# HS-IO-Top.net
KiCad netlist of a schematic drawn in Altium Designer
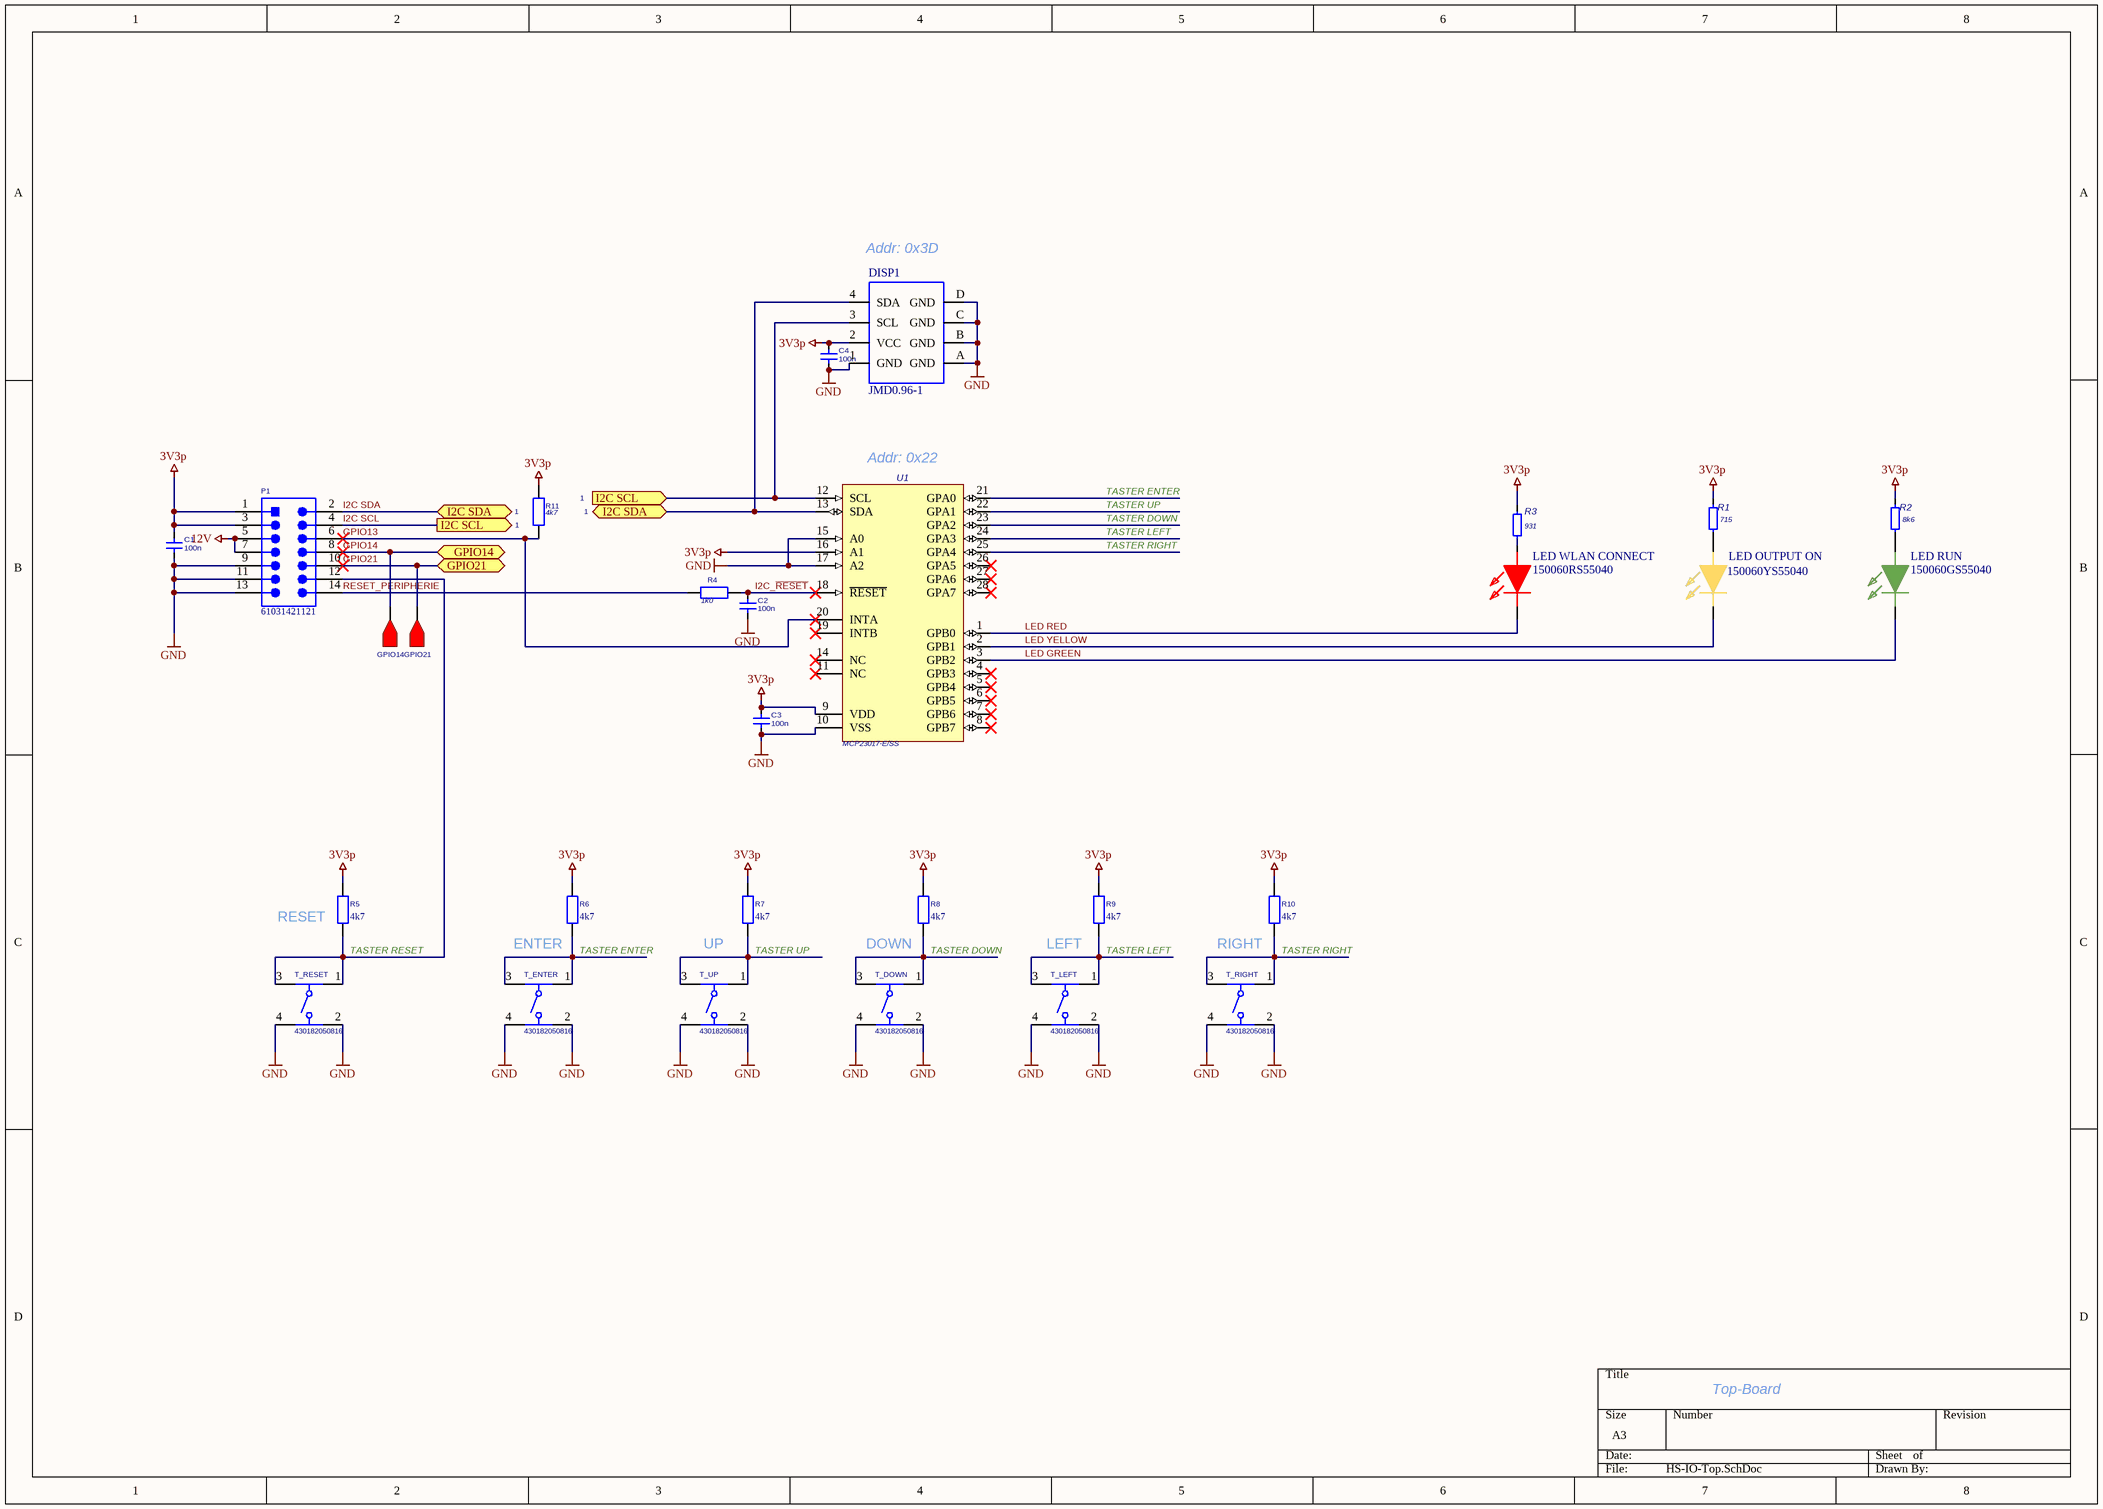
[diagram p0: HS-IO-Top.SchDoc]

(export (version "E")
  (design (tool "Eeschema 10.0.6"))
  (components
    (comp (ref "C1")
      (value "100n")
      (footprint "CC1608-0603")
      (description "SMD0603, X7R, 15%, 50V, 100nF")
      (fields
        (field (name "MANUFACTURER") "KEMET")
        (field (name "MANUFACTURER PART NUMBER") "C0603C104K5RAC7867")
        (field (name "CHECKED") "checked")
      )
      (libsource (lib "FRAKO Kondensatoren- und Anlagenbau GmbH") (part "C_SMD-0603"))
    )
    (comp (ref "C2")
      (value "100n")
      (footprint "CC1608-0603")
      (description "SMD0603, X7R, 15%, 50V, 100nF")
      (fields
        (field (name "MANUFACTURER") "KEMET")
        (field (name "MANUFACTURER PART NUMBER") "C0603C104K5RAC7867")
        (field (name "CHECKED") "checked")
      )
      (libsource (lib "FRAKO Kondensatoren- und Anlagenbau GmbH") (part "C_SMD-0603"))
    )
    (comp (ref "C3")
      (value "100n")
      (footprint "CC1608-0603")
      (description "SMD0603, X7R, 15%, 50V, 100nF")
      (fields
        (field (name "MANUFACTURER") "KEMET")
        (field (name "MANUFACTURER PART NUMBER") "C0603C104K5RAC7867")
        (field (name "CHECKED") "checked")
      )
      (libsource (lib "FRAKO Kondensatoren- und Anlagenbau GmbH") (part "C_SMD-0603"))
    )
    (comp (ref "C4")
      (value "100n")
      (footprint "CC1608-0603")
      (description "SMD0603, X7R, 15%, 50V, 100nF")
      (fields
        (field (name "MANUFACTURER") "KEMET")
        (field (name "MANUFACTURER PART NUMBER") "C0603C104K5RAC7867")
        (field (name "CHECKED") "checked")
      )
      (libsource (lib "FRAKO Kondensatoren- und Anlagenbau GmbH") (part "C_SMD-0603"))
    )
    (comp (ref "DISP1")
      (value "JMD0.96-1")
      (footprint "JMD0.96-1-Footprint-1")
      (description "Monochrome 0.96\" 128x64 I2C OLED Display (Breakout)")
      (libsource (lib "FRAKO Kondensatoren- und Anlagenbau GmbH") (part "I2C-DISPLAY_128x64_0.96"))
    )
    (comp (ref "GPIO14")
      (value "(no part)")
      (footprint "TESTPOINT")
      (description "Test Point")
      (fields (field (name "CHECKED") "checked"))
      (libsource (lib "FRAKO Kondensatoren- und Anlagenbau GmbH") (part "TESTPUNKT_1"))
    )
    (comp (ref "GPIO21")
      (value "(no part)")
      (footprint "TESTPOINT")
      (description "Test Point")
      (fields (field (name "CHECKED") "checked"))
      (libsource (lib "FRAKO Kondensatoren- und Anlagenbau GmbH") (part "TESTPUNKT_1"))
    )
    (comp (ref "LED OUTPUT ON")
      (value "150060YS55040")
      (footprint "LED_0603_Standard")
      (description "LED yellow 0603")
      (fields (field (name "MANUFACTURER") "Würth Elektronik"))
      (libsource (lib "FRAKO Kondensatoren- und Anlagenbau GmbH") (part "150060YS55040"))
    )
    (comp (ref "LED RUN")
      (value "150060GS55040")
      (footprint "LED_0603_Standard")
      (description "LED green 0603")
      (fields (field (name "MANUFACTURER") "Wurth Elektronik"))
      (libsource (lib "FRAKO Kondensatoren- und Anlagenbau GmbH") (part "150060GS55040"))
    )
    (comp (ref "LED WLAN CONNECT")
      (value "150060RS55040")
      (footprint "LED_0603_Standard")
      (description "LED red 0603")
      (fields (field (name "MANUFACTURER") "Würth Elektronik"))
      (libsource (lib "FRAKO Kondensatoren- und Anlagenbau GmbH") (part "150060RS55040"))
    )
    (comp (ref "P1")
      (value "61031421121")
      (footprint "61031421121")
      (description "WR-PHD Pin Header, SMT, pitch 2.54mm, Dual Row, Vertical, 14p")
      (fields (field (name "MANUFACTURER") "Wurth Elektronik"))
      (libsource (lib "FRAKO Kondensatoren- und Anlagenbau GmbH") (part "61031421121"))
    )
    (comp (ref "R1")
      (value "715")
      (footprint "CC1608-0603")
      (description "Resistor 715R 1% 0603")
      (fields
        (field (name "MANUFACTURER") "Vishay / Dale")
        (field (name "MANUFACTURER PART NUMBER") "CRCW0603715RFKEA")
      )
      (libsource (lib "FRAKO Kondensatoren- und Anlagenbau GmbH") (part "RES-EURO-S"))
    )
    (comp (ref "R2")
      (value "8k6")
      (footprint "CC1608-0603")
      (description "Resistor 8k66 1% 0603")
      (fields
        (field (name "MANUFACTURER PART NUMBER") "CRCW06038K66FKEA")
        (field (name "MANUFACTURER") "Vishay / Dale")
      )
      (libsource (lib "FRAKO Kondensatoren- und Anlagenbau GmbH") (part "RES-EURO-S"))
    )
    (comp (ref "R3")
      (value "931")
      (footprint "CC1608-0603")
      (description "Resistor 931R 1% 0603")
      (fields
        (field (name "MANUFACTURER") "Vishay / Dale")
        (field (name "MANUFACTURER PART NUMBER") "CRCW0603931RFKEA")
      )
      (libsource (lib "FRAKO Kondensatoren- und Anlagenbau GmbH") (part "RES-EURO-S"))
    )
    (comp (ref "R4")
      (value "1k0")
      (footprint "CR1608-0603")
      (description "SMD0603, 0.1W, TK100, 1%, 1,0k, Metallfilm")
      (fields
        (field (name "MANUFACTURER") "Vishay / Dale")
        (field (name "MANUFACTURER PART NUMBER") "CRCW06031K00FKEAC")
      )
      (libsource (lib "altium-import") (part "root_2_S0603_1k0_1_1_"))
    )
    (comp (ref "R5")
      (value "4k7")
      (footprint "CR1608-0603")
      (description "SMD0603, 0.1W, TK100, 1%, 4,7k, Metallfilm")
      (fields
        (field (name "MANUFACTURER PART NUMBER") "CRCW06034K70FKEAC")
        (field (name "MANUFACTURER") "Vishay / Dale")
        (field (name "CHECKED") "checked")
      )
      (libsource (lib "FRAKO Kondensatoren- und Anlagenbau GmbH") (part "S0603_27k_1_1"))
    )
    (comp (ref "R6")
      (value "4k7")
      (footprint "CR1608-0603")
      (description "SMD0603, 0.1W, TK100, 1%, 4,7k, Metallfilm")
      (fields
        (field (name "MANUFACTURER PART NUMBER") "CRCW06034K70FKEAC")
        (field (name "MANUFACTURER") "Vishay / Dale")
        (field (name "CHECKED") "checked")
      )
      (libsource (lib "FRAKO Kondensatoren- und Anlagenbau GmbH") (part "S0603_27k_1_1"))
    )
    (comp (ref "R7")
      (value "4k7")
      (footprint "CR1608-0603")
      (description "SMD0603, 0.1W, TK100, 1%, 4,7k, Metallfilm")
      (fields
        (field (name "MANUFACTURER PART NUMBER") "CRCW06034K70FKEAC")
        (field (name "MANUFACTURER") "Vishay / Dale")
        (field (name "CHECKED") "checked")
      )
      (libsource (lib "FRAKO Kondensatoren- und Anlagenbau GmbH") (part "S0603_27k_1_1"))
    )
    (comp (ref "R8")
      (value "4k7")
      (footprint "CR1608-0603")
      (description "SMD0603, 0.1W, TK100, 1%, 4,7k, Metallfilm")
      (fields
        (field (name "MANUFACTURER PART NUMBER") "CRCW06034K70FKEAC")
        (field (name "MANUFACTURER") "Vishay / Dale")
        (field (name "CHECKED") "checked")
      )
      (libsource (lib "FRAKO Kondensatoren- und Anlagenbau GmbH") (part "S0603_27k_1_1"))
    )
    (comp (ref "R9")
      (value "4k7")
      (footprint "CR1608-0603")
      (description "SMD0603, 0.1W, TK100, 1%, 4,7k, Metallfilm")
      (fields
        (field (name "MANUFACTURER PART NUMBER") "CRCW06034K70FKEAC")
        (field (name "MANUFACTURER") "Vishay / Dale")
        (field (name "CHECKED") "checked")
      )
      (libsource (lib "FRAKO Kondensatoren- und Anlagenbau GmbH") (part "S0603_27k_1_1"))
    )
    (comp (ref "R10")
      (value "4k7")
      (footprint "CR1608-0603")
      (description "SMD0603, 0.1W, TK100, 1%, 4,7k, Metallfilm")
      (fields
        (field (name "MANUFACTURER PART NUMBER") "CRCW06034K70FKEAC")
        (field (name "MANUFACTURER") "Vishay / Dale")
        (field (name "CHECKED") "checked")
      )
      (libsource (lib "FRAKO Kondensatoren- und Anlagenbau GmbH") (part "S0603_27k_1_1"))
    )
    (comp (ref "R11")
      (value "4k7")
      (footprint "CR1608-0603")
      (description "SMD0603, 0.1W, TK100, 1%, 4,7k, Metallfilm")
      (fields
        (field (name "MANUFACTURER") "Vishay / Dale")
        (field (name "MANUFACTURER PART NUMBER") "CRCW06034K70FKEAC")
        (field (name "CHECKED") "checked")
      )
      (libsource (lib "") (part "S0603_27k_1_1_1"))
    )
    (comp (ref "T_DOWN")
      (value "430182050816")
      (footprint "430182050816")
      (description "WS-TASV SMT Tact Switch, 6x6x5mm, 160gf")
      (fields (field (name "MANUFACTURER") "Wurth Elektronik"))
      (libsource (lib "FRAKO Kondensatoren- und Anlagenbau GmbH") (part "430182080816"))
    )
    (comp (ref "T_ENTER")
      (value "430182050816")
      (footprint "430182050816")
      (description "WS-TASV SMT Tact Switch, 6x6x5mm, 160gf")
      (fields (field (name "MANUFACTURER") "Wurth Elektronik"))
      (libsource (lib "FRAKO Kondensatoren- und Anlagenbau GmbH") (part "430182080816"))
    )
    (comp (ref "T_LEFT")
      (value "430182050816")
      (footprint "430182050816")
      (description "WS-TASV SMT Tact Switch, 6x6x5mm, 160gf")
      (fields (field (name "MANUFACTURER") "Wurth Elektronik"))
      (libsource (lib "FRAKO Kondensatoren- und Anlagenbau GmbH") (part "430182080816"))
    )
    (comp (ref "T_RESET")
      (value "430182050816")
      (footprint "430182050816")
      (description "WS-TASV SMT Tact Switch, 6x6x5mm, 160gf")
      (fields (field (name "MANUFACTURER") "Wurth Elektronik"))
      (libsource (lib "FRAKO Kondensatoren- und Anlagenbau GmbH") (part "430182080816"))
    )
    (comp (ref "T_RIGHT")
      (value "430182050816")
      (footprint "430182050816")
      (description "WS-TASV SMT Tact Switch, 6x6x5mm, 160gf")
      (fields (field (name "MANUFACTURER") "Wurth Elektronik"))
      (libsource (lib "FRAKO Kondensatoren- und Anlagenbau GmbH") (part "430182080816"))
    )
    (comp (ref "T_UP")
      (value "430182050816")
      (footprint "430182050816")
      (description "WS-TASV SMT Tact Switch, 6x6x5mm, 160gf")
      (fields (field (name "MANUFACTURER") "Wurth Elektronik"))
      (libsource (lib "FRAKO Kondensatoren- und Anlagenbau GmbH") (part "430182080816"))
    )
    (comp (ref "U1")
      (value "MCP23017-E/SS")
      (footprint "SSOP-SS28_M")
      (description "16-Bit I/O Expander with Serial Interface, 28-Pin SSOP, Extended Temperature")
      (fields (field (name "MANUFACTURER") "Microchip"))
      (libsource (lib "FRAKO Kondensatoren- und Anlagenbau GmbH") (part "CMP-0186-00176-2"))
    )
  )
  (nets
    (net (code "2") (name "/GPIO13") (class "Default")
      (node (ref "P1") (pin "6") (pinfunction "6_6") (pintype "passive"))
      (node (ref "R11") (pin "1") (pinfunction "1_1") (pintype "passive"))
      (node (ref "U1") (pin "20") (pinfunction "INTA_20") (pintype "open_collector"))
    )
    (net (code "3") (name "/GPIO14") (class "Default")
      (node (ref "GPIO14") (pin "1") (pintype "passive"))
      (node (ref "P1") (pin "8") (pinfunction "8_8") (pintype "passive"))
    )
    (net (code "4") (name "/GPIO21") (class "Default")
      (node (ref "GPIO21") (pin "1") (pintype "passive"))
      (node (ref "P1") (pin "10") (pinfunction "10_10") (pintype "passive"))
    )
    (net (code "5") (name "/I2C SCL") (class "Default")
      (node (ref "DISP1") (pin "3") (pinfunction "SCL_3") (pintype "passive"))
      (node (ref "P1") (pin "4") (pinfunction "4_4") (pintype "passive"))
      (node (ref "U1") (pin "12") (pinfunction "SCL_12") (pintype "input"))
    )
    (net (code "6") (name "/I2C SDA") (class "Default")
      (node (ref "DISP1") (pin "4") (pinfunction "SDA_4") (pintype "passive"))
      (node (ref "P1") (pin "2") (pinfunction "2_2") (pintype "passive"))
      (node (ref "U1") (pin "13") (pinfunction "SDA_13") (pintype "bidirectional"))
    )
    (net (code "7") (name "/I2C_~{RESET}") (class "Default")
      (node (ref "C2") (pin "2") (pinfunction "2_2") (pintype "passive"))
      (node (ref "R4") (pin "1") (pinfunction "1_1") (pintype "passive"))
      (node (ref "U1") (pin "18") (pinfunction "~{RESET}_18") (pintype "input"))
    )
    (net (code "8") (name "/LED GREEN") (class "Default")
      (node (ref "LED RUN") (pin "1") (pinfunction "K_1") (pintype "passive"))
      (node (ref "U1") (pin "3") (pinfunction "GPB2_3") (pintype "bidirectional"))
    )
    (net (code "9") (name "/LED RED") (class "Default")
      (node (ref "LED WLAN CONNECT") (pin "1") (pinfunction "K_1") (pintype "passive"))
      (node (ref "U1") (pin "1") (pinfunction "GPB0_1") (pintype "bidirectional"))
    )
    (net (code "10") (name "/LED YELLOW") (class "Default")
      (node (ref "LED OUTPUT ON") (pin "1") (pinfunction "K_1") (pintype "passive"))
      (node (ref "U1") (pin "2") (pinfunction "GPB1_2") (pintype "bidirectional"))
    )
    (net (code "11") (name "/RESET_PERIPHERIE") (class "Default")
      (node (ref "P1") (pin "14") (pinfunction "14_14") (pintype "passive"))
      (node (ref "R4") (pin "2") (pinfunction "2_2") (pintype "passive"))
    )
    (net (code "12") (name "/TASTER DOWN") (class "Default")
      (node (ref "R8") (pin "1") (pinfunction "1_1") (pintype "passive"))
      (node (ref "T_DOWN") (pin "1") (pinfunction "1_1") (pintype "passive"))
      (node (ref "T_DOWN") (pin "3") (pinfunction "3_3") (pintype "passive"))
      (node (ref "U1") (pin "23") (pinfunction "GPA2_23") (pintype "bidirectional"))
    )
    (net (code "13") (name "/TASTER ENTER") (class "Default")
      (node (ref "R6") (pin "1") (pinfunction "1_1") (pintype "passive"))
      (node (ref "T_ENTER") (pin "1") (pinfunction "1_1") (pintype "passive"))
      (node (ref "T_ENTER") (pin "3") (pinfunction "3_3") (pintype "passive"))
      (node (ref "U1") (pin "21") (pinfunction "GPA0_21") (pintype "bidirectional"))
    )
    (net (code "14") (name "/TASTER LEFT") (class "Default")
      (node (ref "R9") (pin "1") (pinfunction "1_1") (pintype "passive"))
      (node (ref "T_LEFT") (pin "1") (pinfunction "1_1") (pintype "passive"))
      (node (ref "T_LEFT") (pin "3") (pinfunction "3_3") (pintype "passive"))
      (node (ref "U1") (pin "24") (pinfunction "GPA3_24") (pintype "bidirectional"))
    )
    (net (code "15") (name "/TASTER RESET") (class "Default")
      (node (ref "P1") (pin "12") (pinfunction "12_12") (pintype "passive"))
      (node (ref "R5") (pin "1") (pinfunction "1_1") (pintype "passive"))
      (node (ref "T_RESET") (pin "1") (pinfunction "1_1") (pintype "passive"))
      (node (ref "T_RESET") (pin "3") (pinfunction "3_3") (pintype "passive"))
    )
    (net (code "16") (name "/TASTER RIGHT") (class "Default")
      (node (ref "R10") (pin "1") (pinfunction "1_1") (pintype "passive"))
      (node (ref "T_RIGHT") (pin "1") (pinfunction "1_1") (pintype "passive"))
      (node (ref "T_RIGHT") (pin "3") (pinfunction "3_3") (pintype "passive"))
      (node (ref "U1") (pin "25") (pinfunction "GPA4_25") (pintype "bidirectional"))
    )
    (net (code "17") (name "/TASTER UP") (class "Default")
      (node (ref "R7") (pin "1") (pinfunction "1_1") (pintype "passive"))
      (node (ref "T_UP") (pin "1") (pinfunction "1_1") (pintype "passive"))
      (node (ref "T_UP") (pin "3") (pinfunction "3_3") (pintype "passive"))
      (node (ref "U1") (pin "22") (pinfunction "GPA1_22") (pintype "bidirectional"))
    )
    (net (code "18") (name "3V3p") (class "Default")
      (node (ref "C1") (pin "2") (pinfunction "2_2") (pintype "passive"))
      (node (ref "C3") (pin "2") (pinfunction "2_2") (pintype "passive"))
      (node (ref "C4") (pin "2") (pinfunction "2_2") (pintype "passive"))
      (node (ref "DISP1") (pin "2") (pinfunction "VCC_2") (pintype "passive"))
      (node (ref "P1") (pin "1") (pinfunction "1_1") (pintype "passive"))
      (node (ref "P1") (pin "3") (pinfunction "3_3") (pintype "passive"))
      (node (ref "R1") (pin "2") (pinfunction "2_2") (pintype "passive"))
      (node (ref "R10") (pin "2") (pinfunction "2_2") (pintype "passive"))
      (node (ref "R11") (pin "2") (pinfunction "2_2") (pintype "passive"))
      (node (ref "R2") (pin "2") (pinfunction "2_2") (pintype "passive"))
      (node (ref "R3") (pin "2") (pinfunction "2_2") (pintype "passive"))
      (node (ref "R5") (pin "2") (pinfunction "2_2") (pintype "passive"))
      (node (ref "R6") (pin "2") (pinfunction "2_2") (pintype "passive"))
      (node (ref "R7") (pin "2") (pinfunction "2_2") (pintype "passive"))
      (node (ref "R8") (pin "2") (pinfunction "2_2") (pintype "passive"))
      (node (ref "R9") (pin "2") (pinfunction "2_2") (pintype "passive"))
      (node (ref "U1") (pin "16") (pinfunction "A1_16") (pintype "input"))
      (node (ref "U1") (pin "9") (pinfunction "VDD_9") (pintype "power_in"))
    )
    (net (code "19") (name "12V") (class "Default")
      (node (ref "P1") (pin "5") (pinfunction "5_5") (pintype "passive"))
      (node (ref "P1") (pin "7") (pinfunction "7_7") (pintype "passive"))
    )
    (net (code "20") (name "GND") (class "Default")
      (node (ref "C1") (pin "1") (pinfunction "1_1") (pintype "passive"))
      (node (ref "C2") (pin "1") (pinfunction "1_1") (pintype "passive"))
      (node (ref "C3") (pin "1") (pinfunction "1_1") (pintype "passive"))
      (node (ref "C4") (pin "1") (pinfunction "1_1") (pintype "passive"))
      (node (ref "DISP1") (pin "1") (pinfunction "GND_1") (pintype "passive"))
      (node (ref "DISP1") (pin "A") (pinfunction "GND_A") (pintype "passive"))
      (node (ref "DISP1") (pin "B") (pinfunction "GND_B") (pintype "passive"))
      (node (ref "DISP1") (pin "C") (pinfunction "GND_C") (pintype "passive"))
      (node (ref "DISP1") (pin "D") (pinfunction "GND_D") (pintype "passive"))
      (node (ref "P1") (pin "11") (pinfunction "11_11") (pintype "passive"))
      (node (ref "P1") (pin "13") (pinfunction "13_13") (pintype "passive"))
      (node (ref "P1") (pin "9") (pinfunction "9_9") (pintype "passive"))
      (node (ref "T_DOWN") (pin "2") (pinfunction "2_2") (pintype "passive"))
      (node (ref "T_DOWN") (pin "4") (pinfunction "4_4") (pintype "passive"))
      (node (ref "T_ENTER") (pin "2") (pinfunction "2_2") (pintype "passive"))
      (node (ref "T_ENTER") (pin "4") (pinfunction "4_4") (pintype "passive"))
      (node (ref "T_LEFT") (pin "2") (pinfunction "2_2") (pintype "passive"))
      (node (ref "T_LEFT") (pin "4") (pinfunction "4_4") (pintype "passive"))
      (node (ref "T_RESET") (pin "2") (pinfunction "2_2") (pintype "passive"))
      (node (ref "T_RESET") (pin "4") (pinfunction "4_4") (pintype "passive"))
      (node (ref "T_RIGHT") (pin "2") (pinfunction "2_2") (pintype "passive"))
      (node (ref "T_RIGHT") (pin "4") (pinfunction "4_4") (pintype "passive"))
      (node (ref "T_UP") (pin "2") (pinfunction "2_2") (pintype "passive"))
      (node (ref "T_UP") (pin "4") (pinfunction "4_4") (pintype "passive"))
      (node (ref "U1") (pin "10") (pinfunction "VSS_10") (pintype "power_in"))
      (node (ref "U1") (pin "15") (pinfunction "A0_15") (pintype "input"))
      (node (ref "U1") (pin "17") (pinfunction "A2_17") (pintype "input"))
    )
    (net (code "21") (name "Net-(LED OUTPUT ON-A)") (class "Default")
      (node (ref "LED OUTPUT ON") (pin "2") (pinfunction "A_2") (pintype "passive"))
      (node (ref "R1") (pin "1") (pinfunction "1_1") (pintype "passive"))
    )
    (net (code "22") (name "Net-(LED RUN-A)") (class "Default")
      (node (ref "LED RUN") (pin "2") (pinfunction "A_2") (pintype "passive"))
      (node (ref "R2") (pin "1") (pinfunction "1_1") (pintype "passive"))
    )
    (net (code "23") (name "Net-(LED WLAN CONNECT-A)") (class "Default")
      (node (ref "LED WLAN CONNECT") (pin "2") (pinfunction "A_2") (pintype "passive"))
      (node (ref "R3") (pin "1") (pinfunction "1_1") (pintype "passive"))
    )
    (net (code "24") (name "unconnected-(U1-GPA5-Pad26)") (class "Default")
      (node (ref "U1") (pin "26") (pinfunction "GPA5_26") (pintype "bidirectional+no_connect"))
    )
    (net (code "25") (name "unconnected-(U1-GPA6-Pad27)") (class "Default")
      (node (ref "U1") (pin "27") (pinfunction "GPA6_27") (pintype "bidirectional+no_connect"))
    )
    (net (code "26") (name "unconnected-(U1-GPA7-Pad28)") (class "Default")
      (node (ref "U1") (pin "28") (pinfunction "GPA7_28") (pintype "bidirectional+no_connect"))
    )
    (net (code "27") (name "unconnected-(U1-GPB3-Pad4)") (class "Default")
      (node (ref "U1") (pin "4") (pinfunction "GPB3_4") (pintype "bidirectional+no_connect"))
    )
    (net (code "28") (name "unconnected-(U1-GPB4-Pad5)") (class "Default")
      (node (ref "U1") (pin "5") (pinfunction "GPB4_5") (pintype "bidirectional+no_connect"))
    )
    (net (code "29") (name "unconnected-(U1-GPB5-Pad6)") (class "Default")
      (node (ref "U1") (pin "6") (pinfunction "GPB5_6") (pintype "bidirectional+no_connect"))
    )
    (net (code "30") (name "unconnected-(U1-GPB6-Pad7)") (class "Default")
      (node (ref "U1") (pin "7") (pinfunction "GPB6_7") (pintype "bidirectional+no_connect"))
    )
    (net (code "31") (name "unconnected-(U1-GPB7-Pad8)") (class "Default")
      (node (ref "U1") (pin "8") (pinfunction "GPB7_8") (pintype "bidirectional+no_connect"))
    )
    (net (code "32") (name "unconnected-(U1-INTB-Pad19)") (class "Default")
      (node (ref "U1") (pin "19") (pinfunction "INTB_19") (pintype "open_collector+no_connect"))
    )
    (net (code "33") (name "unconnected-(U1-NC-Pad11)") (class "Default")
      (node (ref "U1") (pin "11") (pinfunction "NC_11") (pintype "passive+no_connect"))
    )
    (net (code "34") (name "unconnected-(U1-NC-Pad14)") (class "Default")
      (node (ref "U1") (pin "14") (pinfunction "NC_14") (pintype "passive+no_connect"))
    )
  )
)
